# 9000H.net
KiCad netlist of a schematic drawn in Altium Designer
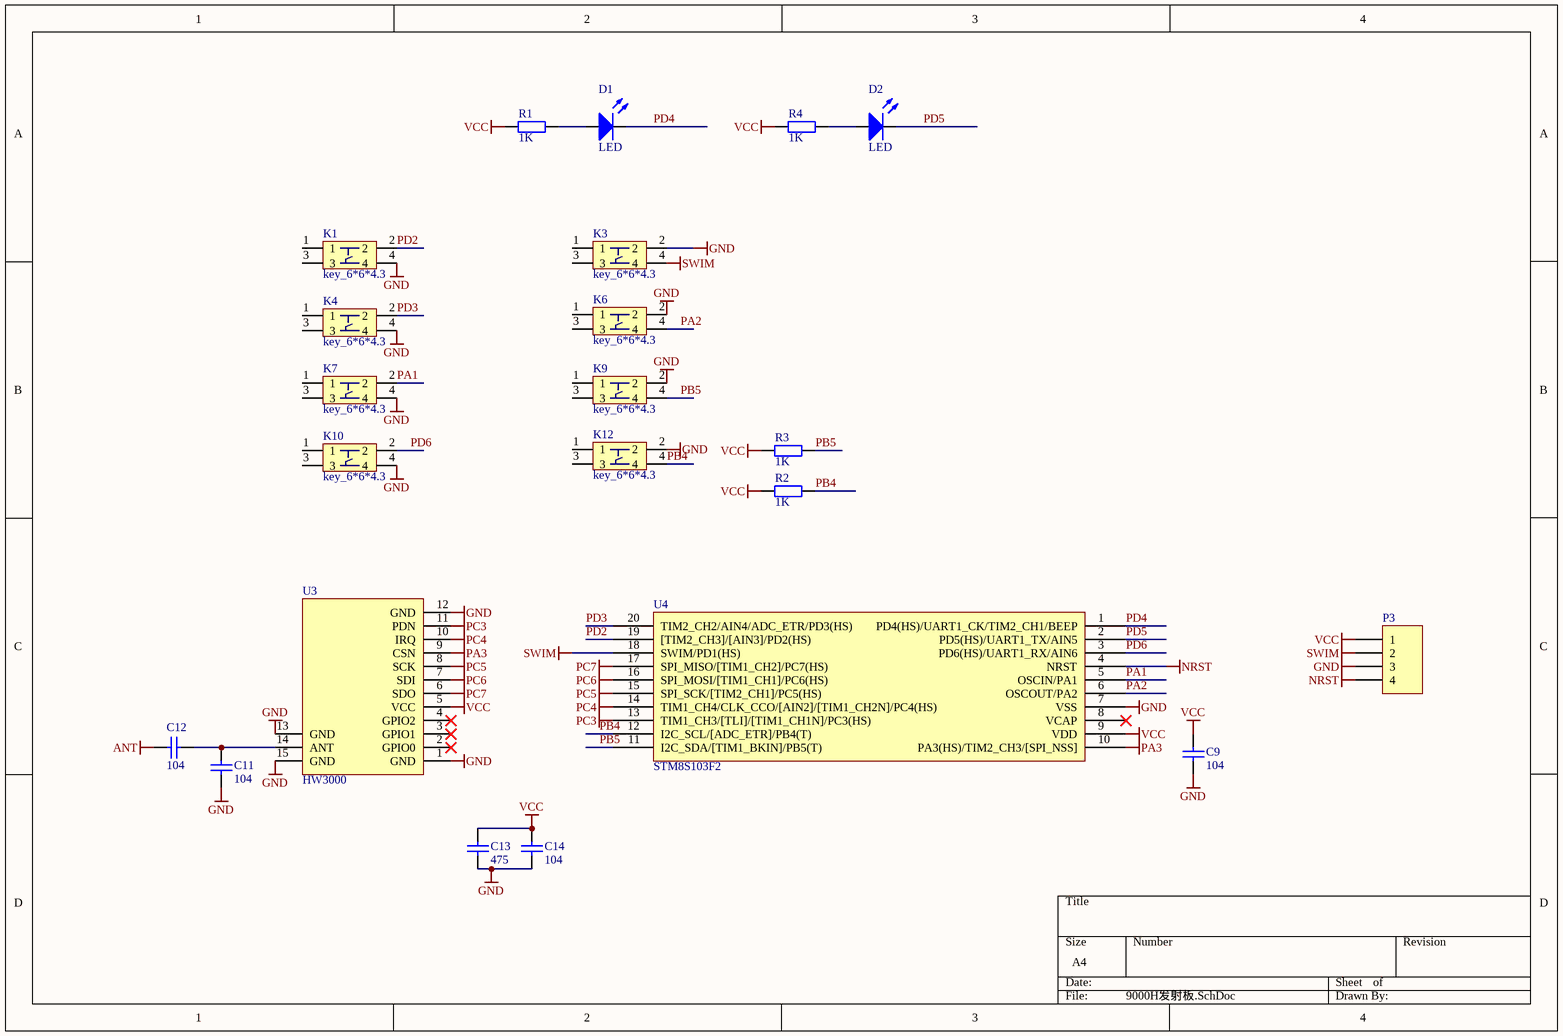
[diagram p0: 9000H发射板.SchDoc]

(export (version "E")
  (design (tool "Eeschema 10.0.6"))
  (components
    (comp (ref "C9")
      (value "104")
      (footprint "0805C")
      (description "无极性电容")
      (libsource (lib "常用器件") (part "Cap"))
    )
    (comp (ref "C11")
      (value "104")
      (footprint "0805C")
      (description "无极性电容")
      (libsource (lib "常用器件") (part "Cap"))
    )
    (comp (ref "C12")
      (value "104")
      (footprint "0805C")
      (description "无极性电容")
      (libsource (lib "常用器件") (part "Cap"))
    )
    (comp (ref "C13")
      (value "475")
      (footprint "0805C")
      (description "无极性电容")
      (libsource (lib "常用器件") (part "Cap"))
    )
    (comp (ref "C14")
      (value "104")
      (footprint "0805C")
      (description "无极性电容")
      (libsource (lib "常用器件") (part "Cap"))
    )
    (comp (ref "D1")
      (value "LED")
      (footprint "0603C")
      (description "发光二极管")
      (libsource (lib "洋哥常用器件") (part "LED_"))
    )
    (comp (ref "D2")
      (value "LED")
      (footprint "0603C")
      (description "发光二极管")
      (libsource (lib "洋哥常用器件") (part "LED_"))
    )
    (comp (ref "K1")
      (value "key_6*6*4.3")
      (footprint "KEY_6*6*4.3")
      (libsource (lib "library") (part "key_6*6*4.3"))
    )
    (comp (ref "K3")
      (value "key_6*6*4.3")
      (footprint "KEY_6*6*4.3")
      (libsource (lib "library") (part "key_6*6*4.3"))
    )
    (comp (ref "K4")
      (value "key_6*6*4.3")
      (footprint "KEY_6*6*4.3")
      (libsource (lib "library") (part "key_6*6*4.3"))
    )
    (comp (ref "K6")
      (value "key_6*6*4.3")
      (footprint "KEY_6*6*4.3")
      (libsource (lib "library") (part "key_6*6*4.3"))
    )
    (comp (ref "K7")
      (value "key_6*6*4.3")
      (footprint "KEY_6*6*4.3")
      (libsource (lib "library") (part "key_6*6*4.3"))
    )
    (comp (ref "K9")
      (value "key_6*6*4.3")
      (footprint "KEY_6*6*4.3")
      (libsource (lib "library") (part "key_6*6*4.3"))
    )
    (comp (ref "K10")
      (value "key_6*6*4.3")
      (footprint "KEY_6*6*4.3")
      (libsource (lib "library") (part "key_6*6*4.3"))
    )
    (comp (ref "K12")
      (value "key_6*6*4.3")
      (footprint "KEY_6*6*4.3")
      (libsource (lib "library") (part "key_6*6*4.3"))
    )
    (comp (ref "P3")
      (value "Header 4")
      (footprint "HDR1X4_3D")
      (description "Header, 4-Pin")
      (fields (field (name "PUBLISHER") "Altium Limited"))
      (libsource (lib "常用连接件") (part "Header 4"))
    )
    (comp (ref "R1")
      (value "1K")
      (footprint "0603R")
      (description "电阻")
      (libsource (lib "洋哥常用器件") (part "Res_"))
    )
    (comp (ref "R2") (value "1K") (footprint "0603R") (description "电阻") (libsource (lib "") (part "Res__1")))
    (comp (ref "R3") (value "1K") (footprint "0603R") (description "电阻") (libsource (lib "") (part "Res__1")))
    (comp (ref "R4")
      (value "1K")
      (footprint "0603R")
      (description "电阻")
      (libsource (lib "洋哥常用器件") (part "Res_"))
    )
    (comp (ref "U3") (value "HW3000") (footprint "HW3000") (libsource (lib "ME") (part "HW3000")))
    (comp (ref "U4")
      (value "STM8S103F2")
      (footprint "SOP20(STM8S)")
      (libsource (lib "ME") (part "STM8S103F2"))
    )
  )
  (nets
    (net (code "1") (name "/PA1") (class "Default")
      (node (ref "K7") (pin "2") (pinfunction "2_2") (pintype "passive"))
      (node (ref "U4") (pin "5") (pinfunction "OSCIN/PA1_5") (pintype "passive"))
    )
    (net (code "2") (name "/PA2") (class "Default")
      (node (ref "K6") (pin "4") (pinfunction "4_4") (pintype "passive"))
      (node (ref "U4") (pin "6") (pinfunction "OSCOUT/PA2_6") (pintype "passive"))
    )
    (net (code "3") (name "/PB4") (class "Default")
      (node (ref "K12") (pin "4") (pinfunction "4_4") (pintype "passive"))
      (node (ref "R2") (pin "1") (pinfunction "1_1") (pintype "passive"))
      (node (ref "U4") (pin "12") (pinfunction "I2C_SCL/[ADC_ETR]/PB4(T)_12") (pintype "passive"))
    )
    (net (code "4") (name "/PB5") (class "Default")
      (node (ref "K9") (pin "4") (pinfunction "4_4") (pintype "passive"))
      (node (ref "R3") (pin "1") (pinfunction "1_1") (pintype "passive"))
      (node (ref "U4") (pin "11") (pinfunction "I2C_SDA/[TIM1_BKIN]/PB5(T)_11") (pintype "passive"))
    )
    (net (code "5") (name "/PD2") (class "Default")
      (node (ref "K1") (pin "2") (pinfunction "2_2") (pintype "passive"))
      (node (ref "U4") (pin "19") (pinfunction "[TIM2_CH3]/[AIN3]/PD2(HS)_19") (pintype "passive"))
    )
    (net (code "6") (name "/PD3") (class "Default")
      (node (ref "K4") (pin "2") (pinfunction "2_2") (pintype "passive"))
      (node (ref "U4") (pin "20") (pinfunction "TIM2_CH2/AIN4/ADC_ETR/PD3(HS)_20") (pintype "passive"))
    )
    (net (code "7") (name "/PD4") (class "Default")
      (node (ref "D1") (pin "2") (pinfunction "K_2") (pintype "passive"))
      (node (ref "U4") (pin "1") (pinfunction "PD4(HS)/UART1_CK/TIM2_CH1/BEEP_1") (pintype "passive"))
    )
    (net (code "8") (name "/PD5") (class "Default")
      (node (ref "D2") (pin "2") (pinfunction "K_2") (pintype "passive"))
      (node (ref "U4") (pin "2") (pinfunction "PD5(HS)/UART1_TX/AIN5_2") (pintype "passive"))
    )
    (net (code "9") (name "/PD6") (class "Default")
      (node (ref "K10") (pin "2") (pinfunction "2_2") (pintype "passive"))
      (node (ref "U4") (pin "3") (pinfunction "PD6(HS)/UART1_RX/AIN6_3") (pintype "passive"))
    )
    (net (code "10") (name "ANT") (class "Default")
      (node (ref "C12") (pin "2") (pinfunction "2_2") (pintype "passive"))
    )
    (net (code "11") (name "GND") (class "Default")
      (node (ref "C11") (pin "1") (pinfunction "1_1") (pintype "passive"))
      (node (ref "C13") (pin "2") (pinfunction "2_2") (pintype "passive"))
      (node (ref "C14") (pin "1") (pinfunction "1_1") (pintype "passive"))
      (node (ref "C9") (pin "1") (pinfunction "1_1") (pintype "passive"))
      (node (ref "K1") (pin "4") (pinfunction "4_4") (pintype "passive"))
      (node (ref "K10") (pin "4") (pinfunction "4_4") (pintype "passive"))
      (node (ref "K12") (pin "2") (pinfunction "2_2") (pintype "passive"))
      (node (ref "K3") (pin "2") (pinfunction "2_2") (pintype "passive"))
      (node (ref "K4") (pin "4") (pinfunction "4_4") (pintype "passive"))
      (node (ref "K6") (pin "2") (pinfunction "2_2") (pintype "passive"))
      (node (ref "K7") (pin "4") (pinfunction "4_4") (pintype "passive"))
      (node (ref "K9") (pin "2") (pinfunction "2_2") (pintype "passive"))
      (node (ref "P3") (pin "3") (pinfunction "3_3") (pintype "passive"))
      (node (ref "U3") (pin "1") (pinfunction "GND_1") (pintype "passive"))
      (node (ref "U3") (pin "12") (pinfunction "GND_12") (pintype "passive"))
      (node (ref "U3") (pin "13") (pinfunction "GND_13") (pintype "passive"))
      (node (ref "U3") (pin "15") (pinfunction "GND_15") (pintype "passive"))
      (node (ref "U4") (pin "7") (pinfunction "VSS_7") (pintype "passive"))
    )
    (net (code "12") (name "NRST") (class "Default")
      (node (ref "P3") (pin "4") (pinfunction "4_4") (pintype "passive"))
      (node (ref "U4") (pin "4") (pinfunction "NRST_4") (pintype "passive"))
    )
    (net (code "13") (name "Net-(D1-A)") (class "Default")
      (node (ref "D1") (pin "1") (pinfunction "A_1") (pintype "passive"))
      (node (ref "R1") (pin "2") (pinfunction "2_2") (pintype "passive"))
    )
    (net (code "14") (name "Net-(D2-A)") (class "Default")
      (node (ref "D2") (pin "1") (pinfunction "A_1") (pintype "passive"))
      (node (ref "R4") (pin "2") (pinfunction "2_2") (pintype "passive"))
    )
    (net (code "15") (name "Net-(U3-ANT)") (class "Default")
      (node (ref "C11") (pin "2") (pinfunction "2_2") (pintype "passive"))
      (node (ref "C12") (pin "1") (pinfunction "1_1") (pintype "passive"))
      (node (ref "U3") (pin "14") (pinfunction "ANT_14") (pintype "passive"))
    )
    (net (code "16") (name "PA3") (class "Default")
      (node (ref "U3") (pin "9") (pinfunction "CSN_9") (pintype "passive"))
      (node (ref "U4") (pin "10") (pinfunction "PA3(HS)/TIM2_CH3/[SPI_NSS]_10") (pintype "passive"))
    )
    (net (code "17") (name "PC3") (class "Default")
      (node (ref "U3") (pin "11") (pinfunction "PDN_11") (pintype "passive"))
      (node (ref "U4") (pin "13") (pinfunction "TIM1_CH3/[TLI]/[TIM1_CH1N]/PC3(HS)_13") (pintype "passive"))
    )
    (net (code "18") (name "PC4") (class "Default")
      (node (ref "U3") (pin "10") (pinfunction "IRQ_10") (pintype "passive"))
      (node (ref "U4") (pin "14") (pinfunction "TIM1_CH4/CLK_CCO/[AIN2]/[TIM1_CH2N]/PC4(HS)_14") (pintype "passive"))
    )
    (net (code "19") (name "PC5") (class "Default")
      (node (ref "U3") (pin "8") (pinfunction "SCK_8") (pintype "passive"))
      (node (ref "U4") (pin "15") (pinfunction "SPI_SCK/[TIM2_CH1]/PC5(HS)_15") (pintype "passive"))
    )
    (net (code "20") (name "PC6") (class "Default")
      (node (ref "U3") (pin "7") (pinfunction "SDI_7") (pintype "passive"))
      (node (ref "U4") (pin "16") (pinfunction "SPI_MOSI/[TIM1_CH1]/PC6(HS)_16") (pintype "passive"))
    )
    (net (code "21") (name "PC7") (class "Default")
      (node (ref "U3") (pin "6") (pinfunction "SDO_6") (pintype "passive"))
      (node (ref "U4") (pin "17") (pinfunction "SPI_MISO/[TIM1_CH2]/PC7(HS)_17") (pintype "passive"))
    )
    (net (code "22") (name "SWIM") (class "Default")
      (node (ref "K3") (pin "4") (pinfunction "4_4") (pintype "passive"))
      (node (ref "P3") (pin "2") (pinfunction "2_2") (pintype "passive"))
      (node (ref "U4") (pin "18") (pinfunction "SWIM/PD1(HS)_18") (pintype "passive"))
    )
    (net (code "23") (name "VCC") (class "Default")
      (node (ref "C13") (pin "1") (pinfunction "1_1") (pintype "passive"))
      (node (ref "C14") (pin "2") (pinfunction "2_2") (pintype "passive"))
      (node (ref "C9") (pin "2") (pinfunction "2_2") (pintype "passive"))
      (node (ref "P3") (pin "1") (pinfunction "1_1") (pintype "passive"))
      (node (ref "R1") (pin "1") (pinfunction "1_1") (pintype "passive"))
      (node (ref "R2") (pin "2") (pinfunction "2_2") (pintype "passive"))
      (node (ref "R3") (pin "2") (pinfunction "2_2") (pintype "passive"))
      (node (ref "R4") (pin "1") (pinfunction "1_1") (pintype "passive"))
      (node (ref "U3") (pin "5") (pinfunction "VCC_5") (pintype "passive"))
      (node (ref "U4") (pin "9") (pinfunction "VDD_9") (pintype "passive"))
    )
    (net (code "24") (name "unconnected-(K1-Pad1)") (class "Default")
      (node (ref "K1") (pin "1") (pinfunction "1_1") (pintype "passive"))
    )
    (net (code "25") (name "unconnected-(K1-Pad3)") (class "Default")
      (node (ref "K1") (pin "3") (pinfunction "3_3") (pintype "passive"))
    )
    (net (code "26") (name "unconnected-(K3-Pad1)") (class "Default")
      (node (ref "K3") (pin "1") (pinfunction "1_1") (pintype "passive"))
    )
    (net (code "27") (name "unconnected-(K3-Pad3)") (class "Default")
      (node (ref "K3") (pin "3") (pinfunction "3_3") (pintype "passive"))
    )
    (net (code "28") (name "unconnected-(K4-Pad1)") (class "Default")
      (node (ref "K4") (pin "1") (pinfunction "1_1") (pintype "passive"))
    )
    (net (code "29") (name "unconnected-(K4-Pad3)") (class "Default")
      (node (ref "K4") (pin "3") (pinfunction "3_3") (pintype "passive"))
    )
    (net (code "30") (name "unconnected-(K6-Pad1)") (class "Default")
      (node (ref "K6") (pin "1") (pinfunction "1_1") (pintype "passive"))
    )
    (net (code "31") (name "unconnected-(K6-Pad3)") (class "Default")
      (node (ref "K6") (pin "3") (pinfunction "3_3") (pintype "passive"))
    )
    (net (code "32") (name "unconnected-(K7-Pad1)") (class "Default")
      (node (ref "K7") (pin "1") (pinfunction "1_1") (pintype "passive"))
    )
    (net (code "33") (name "unconnected-(K7-Pad3)") (class "Default")
      (node (ref "K7") (pin "3") (pinfunction "3_3") (pintype "passive"))
    )
    (net (code "34") (name "unconnected-(K9-Pad1)") (class "Default")
      (node (ref "K9") (pin "1") (pinfunction "1_1") (pintype "passive"))
    )
    (net (code "35") (name "unconnected-(K9-Pad3)") (class "Default")
      (node (ref "K9") (pin "3") (pinfunction "3_3") (pintype "passive"))
    )
    (net (code "36") (name "unconnected-(K10-Pad1)") (class "Default")
      (node (ref "K10") (pin "1") (pinfunction "1_1") (pintype "passive"))
    )
    (net (code "37") (name "unconnected-(K10-Pad3)") (class "Default")
      (node (ref "K10") (pin "3") (pinfunction "3_3") (pintype "passive"))
    )
    (net (code "38") (name "unconnected-(K12-Pad1)") (class "Default")
      (node (ref "K12") (pin "1") (pinfunction "1_1") (pintype "passive"))
    )
    (net (code "39") (name "unconnected-(K12-Pad3)") (class "Default")
      (node (ref "K12") (pin "3") (pinfunction "3_3") (pintype "passive"))
    )
    (net (code "40") (name "unconnected-(U3-GPIO0-Pad2)") (class "Default")
      (node (ref "U3") (pin "2") (pinfunction "GPIO0_2") (pintype "passive+no_connect"))
    )
    (net (code "41") (name "unconnected-(U3-GPIO1-Pad3)") (class "Default")
      (node (ref "U3") (pin "3") (pinfunction "GPIO1_3") (pintype "passive+no_connect"))
    )
    (net (code "42") (name "unconnected-(U3-GPIO2-Pad4)") (class "Default")
      (node (ref "U3") (pin "4") (pinfunction "GPIO2_4") (pintype "passive+no_connect"))
    )
    (net (code "43") (name "unconnected-(U4-VCAP-Pad8)") (class "Default")
      (node (ref "U4") (pin "8") (pinfunction "VCAP_8") (pintype "passive+no_connect"))
    )
  )
)
